# Breakout_FPGA.net
KiCad netlist of a schematic drawn in Altium Designer
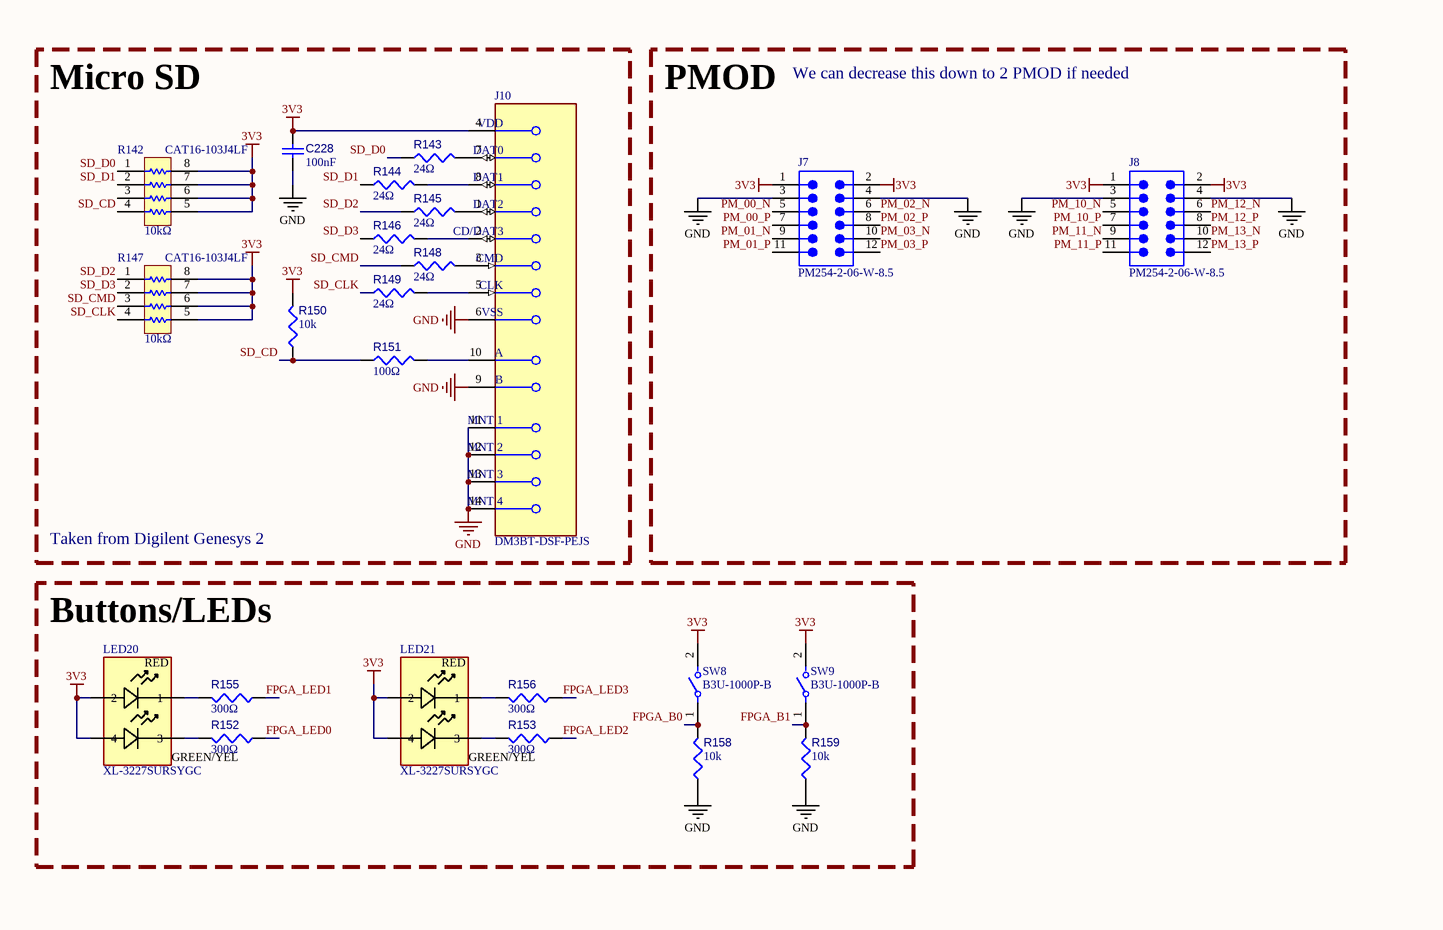
[diagram p0: Breakout_FPGA.SchDoc, left]
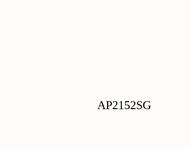
[diagram p1: Breakout_FPGA.SchDoc, right]

(export (version "E")
  (design (tool "Eeschema 10.0.6"))
  (components
    (comp (ref "C228")
      (value "100nF")
      (footprint "CAP-0402-MFG")
      (description "0402-100n-10%-25V-X7R-AECQ200")
      (fields (field (name "TOLERANCE") "10%") (field (name "MANUFACTURER PART NUMBER") "CL05B104KA54PNC"))
      (libsource (lib "UC Berkeley – EE194") (part "CAP-NP-2P"))
    )
    (comp (ref "J7")
      (value "PM254-2-06-W-8.5")
      (footprint "2x6-RA-FEM-2.54mm-CONN")
      (description "Pin Header, Board-to-Board, 2.54 mm, 2 Rows, 12 Contacts, Through Hole, TSW Series")
      (libsource (lib "UC Berkeley – EE194") (part "SMTC-TSW-106-07-X-D"))
    )
    (comp (ref "J8")
      (value "PM254-2-06-W-8.5")
      (footprint "2x6-RA-FEM-2.54mm-CONN")
      (description "Pin Header, Board-to-Board, 2.54 mm, 2 Rows, 12 Contacts, Through Hole, TSW Series")
      (libsource (lib "UC Berkeley – EE194") (part "SMTC-TSW-106-07-X-D"))
    )
    (comp (ref "J10")
      (value "DM3BT-DSF-PEJS")
      (footprint "MICROSD-10(8+2)-MFG")
      (description "Memory Card Connector, MicroSD, Push-Push, 8 Contacts, Copper Alloy, Gold Plated Contacts, DM3")
      (libsource (lib "UC Berkeley – EE194") (part "MICROSD"))
    )
    (comp (ref "LED20")
      (value "XL-3227SURSYGC")
      (footprint "LED-1210-4P-MFG")
      (description "LED indicator light dual color red yellow green 1210 front facing")
      (libsource (lib "UC Berkeley – EE194") (part "LED-2COLOR-4P"))
    )
    (comp (ref "LED21")
      (value "XL-3227SURSYGC")
      (footprint "LED-1210-4P-MFG")
      (description "LED indicator light dual color red yellow green 1210 front facing")
      (libsource (lib "UC Berkeley – EE194") (part "LED-2COLOR-4P"))
    )
    (comp (ref "R142")
      (value "CAT16-103J4LF")
      (footprint "RES-4x0603-MFG")
      (description "Res Thick Film Array 10K Ohm 5% 0.25W(1/4W) ±200ppm/C ISOL 8-Pin 1206(4 X 0603) Concave SMD T/R")
      (fields (field (name "TOLERANCE") "5%") (field (name "ALTIUM_VALUE") "10kΩ"))
      (libsource (lib "UC Berkeley – EE194") (part "RES-x4-8P"))
    )
    (comp (ref "R143")
      (value "24Ω")
      (footprint "RES-0402")
      (description "0402-24-1%-1/16W-AEC-Q200")
      (fields (field (name "TOLERANCE") "1%") (field (name "MANUFACTURER PART NUMBER") "AC0402FR-0724RL"))
      (libsource (lib "UC Berkeley – EE194") (part "RES-2P"))
    )
    (comp (ref "R144")
      (value "24Ω")
      (footprint "RES-0402")
      (description "0402-24-1%-1/16W-AEC-Q200")
      (fields (field (name "TOLERANCE") "1%") (field (name "MANUFACTURER PART NUMBER") "AC0402FR-0724RL"))
      (libsource (lib "UC Berkeley – EE194") (part "RES-2P"))
    )
    (comp (ref "R145")
      (value "24Ω")
      (footprint "RES-0402")
      (description "0402-24-1%-1/16W-AEC-Q200")
      (fields (field (name "TOLERANCE") "1%") (field (name "MANUFACTURER PART NUMBER") "AC0402FR-0724RL"))
      (libsource (lib "UC Berkeley – EE194") (part "RES-2P"))
    )
    (comp (ref "R146")
      (value "24Ω")
      (footprint "RES-0402")
      (description "0402-24-1%-1/16W-AEC-Q200")
      (fields (field (name "TOLERANCE") "1%") (field (name "MANUFACTURER PART NUMBER") "AC0402FR-0724RL"))
      (libsource (lib "UC Berkeley – EE194") (part "RES-2P"))
    )
    (comp (ref "R147")
      (value "CAT16-103J4LF")
      (footprint "RES-4x0603-MFG")
      (description "Res Thick Film Array 10K Ohm 5% 0.25W(1/4W) ±200ppm/C ISOL 8-Pin 1206(4 X 0603) Concave SMD T/R")
      (fields (field (name "TOLERANCE") "5%") (field (name "ALTIUM_VALUE") "10kΩ"))
      (libsource (lib "UC Berkeley – EE194") (part "RES-x4-8P"))
    )
    (comp (ref "R148")
      (value "24Ω")
      (footprint "RES-0402")
      (description "0402-24-1%-1/16W-AEC-Q200")
      (fields (field (name "TOLERANCE") "1%") (field (name "MANUFACTURER PART NUMBER") "AC0402FR-0724RL"))
      (libsource (lib "UC Berkeley – EE194") (part "RES-2P"))
    )
    (comp (ref "R149")
      (value "24Ω")
      (footprint "RES-0402")
      (description "0402-24-1%-1/16W-AEC-Q200")
      (fields (field (name "TOLERANCE") "1%") (field (name "MANUFACTURER PART NUMBER") "AC0402FR-0724RL"))
      (libsource (lib "UC Berkeley – EE194") (part "RES-2P"))
    )
    (comp (ref "R150")
      (value "10k")
      (footprint "RES-0402")
      (description "0402-10k-1%-1/16W-AEC-Q200")
      (fields (field (name "TOLERANCE") "1%") (field (name "MANUFACTURER PART NUMBER") "AC0402FR-0710KL"))
      (libsource (lib "UC Berkeley – EE194") (part "RES-2P"))
    )
    (comp (ref "R151")
      (value "100Ω")
      (footprint "RES-0402")
      (description "0402-100-1%-1/16W-AEC-Q200")
      (fields (field (name "MANUFACTURER PART NUMBER") "AC0402FR-07100RL") (field (name "POWER") "63mW"))
      (libsource (lib "UC Berkeley – EE194") (part "RES-2P"))
    )
    (comp (ref "R152")
      (value "300Ω")
      (footprint "RES-0402")
      (description "0402-300-1%-1/16W-AEC-Q200")
      (fields (field (name "MANUFACTURER PART NUMBER") "AC0402FR-07300RL") (field (name "POWER") "63mW"))
      (libsource (lib "UC Berkeley – EE194") (part "RES-2P"))
    )
    (comp (ref "R153")
      (value "300Ω")
      (footprint "RES-0402")
      (description "0402-300-1%-1/16W-AEC-Q200")
      (fields (field (name "MANUFACTURER PART NUMBER") "AC0402FR-07300RL") (field (name "POWER") "63mW"))
      (libsource (lib "UC Berkeley – EE194") (part "RES-2P"))
    )
    (comp (ref "R155")
      (value "300Ω")
      (footprint "RES-0402")
      (description "0402-300-1%-1/16W-AEC-Q200")
      (fields (field (name "MANUFACTURER PART NUMBER") "AC0402FR-07300RL") (field (name "POWER") "63mW"))
      (libsource (lib "UC Berkeley – EE194") (part "RES-2P"))
    )
    (comp (ref "R156")
      (value "300Ω")
      (footprint "RES-0402")
      (description "0402-300-1%-1/16W-AEC-Q200")
      (fields (field (name "MANUFACTURER PART NUMBER") "AC0402FR-07300RL") (field (name "POWER") "63mW"))
      (libsource (lib "UC Berkeley – EE194") (part "RES-2P"))
    )
    (comp (ref "R158")
      (value "10k")
      (footprint "RES-0402")
      (description "0402-10k-1%-1/16W-AEC-Q200")
      (fields (field (name "TOLERANCE") "1%") (field (name "MANUFACTURER PART NUMBER") "AC0402FR-0710KL"))
      (libsource (lib "UC Berkeley – EE194") (part "RES-2P"))
    )
    (comp (ref "R159")
      (value "10k")
      (footprint "RES-0402")
      (description "0402-10k-1%-1/16W-AEC-Q200")
      (fields (field (name "TOLERANCE") "1%") (field (name "MANUFACTURER PART NUMBER") "AC0402FR-0710KL"))
      (libsource (lib "UC Berkeley – EE194") (part "RES-2P"))
    )
    (comp (ref "SW8")
      (value "B3U-1000P-B")
      (footprint "FP-B3U-1000P-B-MFG")
      (description "Switch Tactile N.O. SPST Round Button Gull Wing 0.05A 12VDC 1.5N SMD Embossed T/R")
      (libsource (lib "UC Berkeley – EE194") (part "SWITCH-SPST-OFF-MOM-2P"))
    )
    (comp (ref "SW9")
      (value "B3U-1000P-B")
      (footprint "FP-B3U-1000P-B-MFG")
      (description "Switch Tactile N.O. SPST Round Button Gull Wing 0.05A 12VDC 1.5N SMD Embossed T/R")
      (libsource (lib "UC Berkeley – EE194") (part "SWITCH-SPST-OFF-MOM-2P"))
    )
  )
  (nets
    (net (code "1") (name "/FPGA_B0") (class "Default")
      (node (ref "R158") (pin "2") (pinfunction "2_2") (pintype "passive"))
      (node (ref "SW8") (pin "1") (pinfunction "1_1") (pintype "passive"))
    )
    (net (code "2") (name "/FPGA_B1") (class "Default")
      (node (ref "R159") (pin "2") (pinfunction "2_2") (pintype "passive"))
      (node (ref "SW9") (pin "1") (pinfunction "1_1") (pintype "passive"))
    )
    (net (code "3") (name "/FPGA_LED0") (class "Default")
      (node (ref "R152") (pin "2") (pinfunction "2_2") (pintype "passive"))
    )
    (net (code "4") (name "/FPGA_LED1") (class "Default")
      (node (ref "R155") (pin "2") (pinfunction "2_2") (pintype "passive"))
    )
    (net (code "5") (name "/FPGA_LED2") (class "Default")
      (node (ref "R153") (pin "2") (pinfunction "2_2") (pintype "passive"))
    )
    (net (code "6") (name "/FPGA_LED3") (class "Default")
      (node (ref "R156") (pin "2") (pinfunction "2_2") (pintype "passive"))
    )
    (net (code "7") (name "/PM_00_N") (class "Default")
      (node (ref "J7") (pin "5") (pinfunction "5_5") (pintype "passive"))
    )
    (net (code "8") (name "/PM_00_P") (class "Default")
      (node (ref "J7") (pin "7") (pinfunction "7_7") (pintype "passive"))
    )
    (net (code "9") (name "/PM_01_N") (class "Default")
      (node (ref "J7") (pin "9") (pinfunction "9_9") (pintype "passive"))
    )
    (net (code "10") (name "/PM_01_P") (class "Default")
      (node (ref "J7") (pin "11") (pinfunction "11_11") (pintype "passive"))
    )
    (net (code "11") (name "/PM_02_N") (class "Default")
      (node (ref "J7") (pin "6") (pinfunction "6_6") (pintype "passive"))
    )
    (net (code "12") (name "/PM_02_P") (class "Default")
      (node (ref "J7") (pin "8") (pinfunction "8_8") (pintype "passive"))
    )
    (net (code "13") (name "/PM_03_N") (class "Default")
      (node (ref "J7") (pin "10") (pinfunction "10_10") (pintype "passive"))
    )
    (net (code "14") (name "/PM_03_P") (class "Default")
      (node (ref "J7") (pin "12") (pinfunction "12_12") (pintype "passive"))
    )
    (net (code "15") (name "/PM_10_N") (class "Default")
      (node (ref "J8") (pin "5") (pinfunction "5_5") (pintype "passive"))
    )
    (net (code "16") (name "/PM_10_P") (class "Default")
      (node (ref "J8") (pin "7") (pinfunction "7_7") (pintype "passive"))
    )
    (net (code "17") (name "/PM_11_N") (class "Default")
      (node (ref "J8") (pin "9") (pinfunction "9_9") (pintype "passive"))
    )
    (net (code "18") (name "/PM_11_P") (class "Default")
      (node (ref "J8") (pin "11") (pinfunction "11_11") (pintype "passive"))
    )
    (net (code "19") (name "/PM_12_N") (class "Default")
      (node (ref "J8") (pin "6") (pinfunction "6_6") (pintype "passive"))
    )
    (net (code "20") (name "/PM_12_P") (class "Default")
      (node (ref "J8") (pin "8") (pinfunction "8_8") (pintype "passive"))
    )
    (net (code "21") (name "/PM_13_N") (class "Default")
      (node (ref "J8") (pin "10") (pinfunction "10_10") (pintype "passive"))
    )
    (net (code "22") (name "/PM_13_P") (class "Default")
      (node (ref "J8") (pin "12") (pinfunction "12_12") (pintype "passive"))
    )
    (net (code "23") (name "/SD_CD") (class "Default")
      (node (ref "R142") (pin "4") (pinfunction "4_4") (pintype "passive"))
      (node (ref "R150") (pin "1") (pinfunction "1_1") (pintype "passive"))
      (node (ref "R151") (pin "1") (pinfunction "1_1") (pintype "passive"))
    )
    (net (code "24") (name "/SD_CLK") (class "Default")
      (node (ref "R147") (pin "4") (pinfunction "4_4") (pintype "passive"))
      (node (ref "R149") (pin "1") (pinfunction "1_1") (pintype "passive"))
    )
    (net (code "25") (name "/SD_CMD") (class "Default")
      (node (ref "R147") (pin "3") (pinfunction "3_3") (pintype "passive"))
      (node (ref "R148") (pin "1") (pinfunction "1_1") (pintype "passive"))
    )
    (net (code "26") (name "/SD_D0") (class "Default")
      (node (ref "R142") (pin "1") (pinfunction "1_1") (pintype "passive"))
      (node (ref "R143") (pin "1") (pinfunction "1_1") (pintype "passive"))
    )
    (net (code "27") (name "/SD_D1") (class "Default")
      (node (ref "R142") (pin "2") (pinfunction "2_2") (pintype "passive"))
      (node (ref "R144") (pin "1") (pinfunction "1_1") (pintype "passive"))
    )
    (net (code "28") (name "/SD_D2") (class "Default")
      (node (ref "R145") (pin "1") (pinfunction "1_1") (pintype "passive"))
      (node (ref "R147") (pin "1") (pinfunction "1_1") (pintype "passive"))
    )
    (net (code "29") (name "/SD_D3") (class "Default")
      (node (ref "R146") (pin "1") (pinfunction "1_1") (pintype "passive"))
      (node (ref "R147") (pin "2") (pinfunction "2_2") (pintype "passive"))
    )
    (net (code "30") (name "3V3") (class "Default")
      (node (ref "C228") (pin "1") (pinfunction "1_1") (pintype "passive"))
      (node (ref "J10") (pin "4") (pinfunction "VDD_4") (pintype "power_in"))
      (node (ref "J7") (pin "1") (pinfunction "1_1") (pintype "passive"))
      (node (ref "J7") (pin "2") (pinfunction "2_2") (pintype "passive"))
      (node (ref "J8") (pin "1") (pinfunction "1_1") (pintype "passive"))
      (node (ref "J8") (pin "2") (pinfunction "2_2") (pintype "passive"))
      (node (ref "LED20") (pin "2") (pinfunction "2_2") (pintype "passive"))
      (node (ref "LED20") (pin "4") (pinfunction "4_4") (pintype "passive"))
      (node (ref "LED21") (pin "2") (pinfunction "2_2") (pintype "passive"))
      (node (ref "LED21") (pin "4") (pinfunction "4_4") (pintype "passive"))
      (node (ref "R142") (pin "5") (pinfunction "5_5") (pintype "passive"))
      (node (ref "R142") (pin "6") (pinfunction "6_6") (pintype "passive"))
      (node (ref "R142") (pin "7") (pinfunction "7_7") (pintype "passive"))
      (node (ref "R142") (pin "8") (pinfunction "8_8") (pintype "passive"))
      (node (ref "R147") (pin "5") (pinfunction "5_5") (pintype "passive"))
      (node (ref "R147") (pin "6") (pinfunction "6_6") (pintype "passive"))
      (node (ref "R147") (pin "7") (pinfunction "7_7") (pintype "passive"))
      (node (ref "R147") (pin "8") (pinfunction "8_8") (pintype "passive"))
      (node (ref "R150") (pin "2") (pinfunction "2_2") (pintype "passive"))
      (node (ref "SW8") (pin "2") (pinfunction "2_2") (pintype "passive"))
      (node (ref "SW9") (pin "2") (pinfunction "2_2") (pintype "passive"))
    )
    (net (code "31") (name "GND") (class "Default")
      (node (ref "C228") (pin "2") (pinfunction "2_2") (pintype "passive"))
      (node (ref "J10") (pin "11") (pinfunction "MNT_1_11") (pintype "passive"))
      (node (ref "J10") (pin "12") (pinfunction "MNT_2_12") (pintype "passive"))
      (node (ref "J10") (pin "13") (pinfunction "MNT_3_13") (pintype "passive"))
      (node (ref "J10") (pin "14") (pinfunction "MNT_4_14") (pintype "passive"))
      (node (ref "J10") (pin "6") (pinfunction "VSS_6") (pintype "power_in"))
      (node (ref "J10") (pin "9") (pinfunction "B_9") (pintype "passive"))
      (node (ref "J7") (pin "3") (pinfunction "3_3") (pintype "passive"))
      (node (ref "J7") (pin "4") (pinfunction "4_4") (pintype "passive"))
      (node (ref "J8") (pin "3") (pinfunction "3_3") (pintype "passive"))
      (node (ref "J8") (pin "4") (pinfunction "4_4") (pintype "passive"))
      (node (ref "R158") (pin "1") (pinfunction "1_1") (pintype "passive"))
      (node (ref "R159") (pin "1") (pinfunction "1_1") (pintype "passive"))
    )
    (net (code "32") (name "Net-(J10-A)") (class "Default")
      (node (ref "J10") (pin "10") (pinfunction "A_10") (pintype "passive"))
      (node (ref "R151") (pin "2") (pinfunction "2_2") (pintype "passive"))
    )
    (net (code "33") (name "Net-(J10-CD{slash}DAT3)") (class "Default")
      (node (ref "J10") (pin "2") (pinfunction "CD/DAT3_2") (pintype "bidirectional"))
      (node (ref "R146") (pin "2") (pinfunction "2_2") (pintype "passive"))
    )
    (net (code "34") (name "Net-(J10-CLK)") (class "Default")
      (node (ref "J10") (pin "5") (pinfunction "CLK_5") (pintype "input"))
      (node (ref "R149") (pin "2") (pinfunction "2_2") (pintype "passive"))
    )
    (net (code "35") (name "Net-(J10-CMD)") (class "Default")
      (node (ref "J10") (pin "3") (pinfunction "CMD_3") (pintype "input"))
      (node (ref "R148") (pin "2") (pinfunction "2_2") (pintype "passive"))
    )
    (net (code "36") (name "Net-(J10-DAT0)") (class "Default")
      (node (ref "J10") (pin "7") (pinfunction "DAT0_7") (pintype "bidirectional"))
      (node (ref "R143") (pin "2") (pinfunction "2_2") (pintype "passive"))
    )
    (net (code "37") (name "Net-(J10-DAT1)") (class "Default")
      (node (ref "J10") (pin "8") (pinfunction "DAT1_8") (pintype "bidirectional"))
      (node (ref "R144") (pin "2") (pinfunction "2_2") (pintype "passive"))
    )
    (net (code "38") (name "Net-(J10-DAT2)") (class "Default")
      (node (ref "J10") (pin "1") (pinfunction "DAT2_1") (pintype "bidirectional"))
      (node (ref "R145") (pin "2") (pinfunction "2_2") (pintype "passive"))
    )
    (net (code "39") (name "Net-(LED20-Pad1)") (class "Default")
      (node (ref "LED20") (pin "1") (pinfunction "1_1") (pintype "passive"))
      (node (ref "R155") (pin "1") (pinfunction "1_1") (pintype "passive"))
    )
    (net (code "40") (name "Net-(LED20-Pad3)") (class "Default")
      (node (ref "LED20") (pin "3") (pinfunction "3_3") (pintype "passive"))
      (node (ref "R152") (pin "1") (pinfunction "1_1") (pintype "passive"))
    )
    (net (code "41") (name "Net-(LED21-Pad1)") (class "Default")
      (node (ref "LED21") (pin "1") (pinfunction "1_1") (pintype "passive"))
      (node (ref "R156") (pin "1") (pinfunction "1_1") (pintype "passive"))
    )
    (net (code "42") (name "Net-(LED21-Pad3)") (class "Default")
      (node (ref "LED21") (pin "3") (pinfunction "3_3") (pintype "passive"))
      (node (ref "R153") (pin "1") (pinfunction "1_1") (pintype "passive"))
    )
    (net (code "43") (name "unconnected-(R142-Pad3)") (class "Default")
      (node (ref "R142") (pin "3") (pinfunction "3_3") (pintype "passive"))
    )
  )
)
